# design.net
KiCad netlist of a schematic drawn in Altium Designer
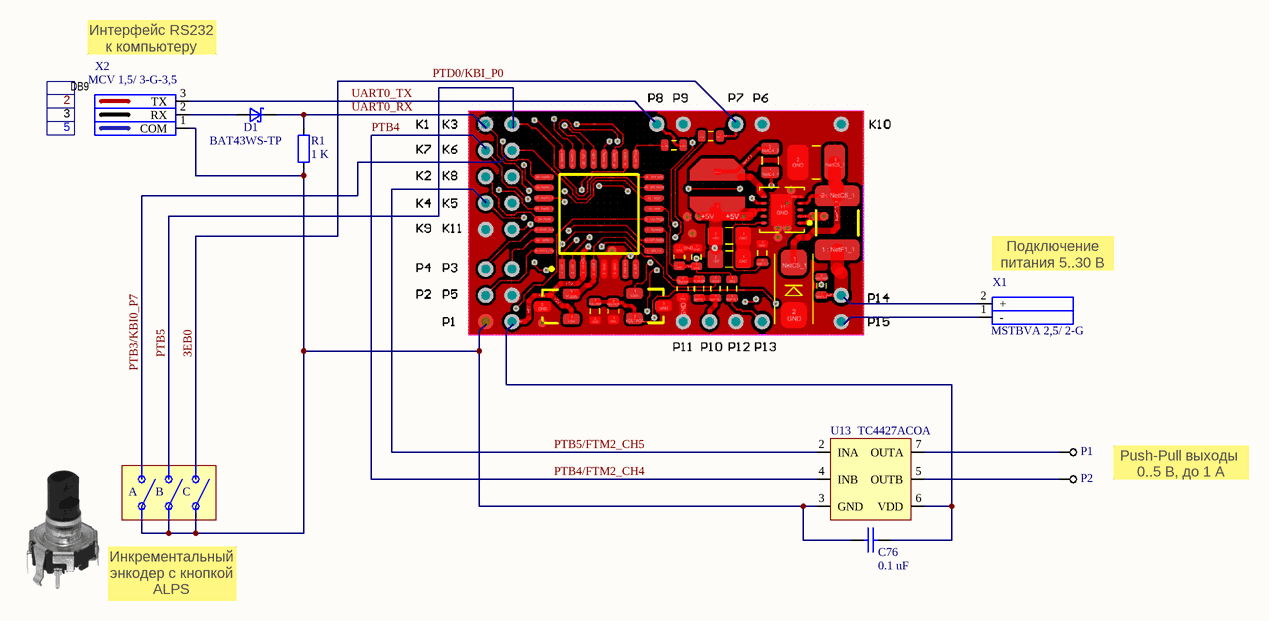
[diagram p0: Макет генератора сигналов.SchDoc]

(export (version "E")
  (design (tool "Eeschema 10.0.6"))
  (components
    (comp (ref "C76")
      (value "0.1 uF")
      (footprint "1608[0603]")
      (description "0.1 uF, 25V, 10% , X7R,  0603 SMD MLC Capacitor")
      (fields (field (name "TOLERANCE") "10%") (field (name "MANUFACTURER") "SAMSUNG"))
      (libsource (lib "ea_Capacitors") (part "CVNF100K0603-25"))
    )
    (comp (ref "D1")
      (value "BAT43WS-TP")
      (footprint "SOD323")
      (description "Schottky 30V 200 mA SOD323")
      (fields
        (field (name "MANUFACTURER") "Micro Commercial Co.")
        (field (name "PARTNUM") "BAT43WSTPMSCT-ND")
      )
      (libsource (lib "ea_Diodes") (part "BAT43WS-TP"))
    )
    (comp (ref "P1")
      (value "Pin 0.7 mm")
      (footprint "Mount hole 0.7 mm")
      (libsource (lib "ea_Connectors") (part "Pin 0.7 mm"))
    )
    (comp (ref "P2")
      (value "Pin 0.7 mm")
      (footprint "Mount hole 0.7 mm")
      (libsource (lib "ea_Connectors") (part "Pin 0.7 mm"))
    )
    (comp (ref "R1")
      (value "1 K")
      (footprint "0603")
      (description "1 K, 1%, 0603, SMD Resistor, Taped")
      (fields (field (name "MANUFACTURER") "Vishay") (field (name "TOLERANCE") "1%"))
      (libsource (lib "ea_Resistors") (part "RL0603K001-1"))
    )
    (comp (ref "U13")
      (value "TC4427ACOA")
      (footprint "SO-8")
      (description "MOSFET drv 1.5A dual, 4.5-18 V,   8SOIC, 0-70 C")
      (fields (field (name "MANUFACTURER") "Microchip Technology") (field (name "PARTNUM") "TC4427ACOA-ND"))
      (libsource (lib "ea_IC_registers_buffers") (part "TC4427ACOA"))
    )
    (comp (ref "X1")
      (value "MSTBVA 2,5/ 2-G")
      (footprint "CIM020P1")
      (description "TERM BLOCK HEADER 2POS 5.0MM")
      (fields (field (name "MANUFACTURER") "Phoenix Contact") (field (name "PARTNUM") "1755516"))
      (libsource (lib "ea_Connectors") (part "796636-2"))
    )
    (comp (ref "X2")
      (value "MCV 1,5/ 3-G-3,5")
      (footprint "mcv1.5-3-g_3.5")
      (description "Header, 8 A, 160 V, 3.5 mm pitch, 3 pos")
      (fields (field (name "MANUFACTURER") "Phoenix Contact") (field (name "PARTNUM") "1843619"))
      (libsource (lib "ea_Connectors") (part "MCV1.5/3-G-3.5"))
    )
  )
  (nets
    (net (code "2") (name "/PTB4") (class "Default")
      (node (ref "U13") (pin "4") (pinfunction "INB_4") (pintype "passive"))
    )
    (net (code "4") (name "/PTB5{slash}FTM2_CH5") (class "Default")
      (node (ref "U13") (pin "2") (pinfunction "INA_2") (pintype "passive"))
    )
    (net (code "6") (name "/UART0_RX") (class "Default")
      (node (ref "D1") (pin "2") (pinfunction "C_2") (pintype "passive"))
      (node (ref "R1") (pin "2") (pinfunction "2_2") (pintype "passive"))
    )
    (net (code "7") (name "/UART0_TX") (class "Default")
      (node (ref "X2") (pin "3") (pinfunction "TX_3") (pintype "passive"))
    )
    (net (code "8") (name "Net-(D1-A)") (class "Default")
      (node (ref "D1") (pin "1") (pinfunction "A_1") (pintype "passive"))
      (node (ref "X2") (pin "2") (pinfunction "RX_2") (pintype "passive"))
    )
    (net (code "9") (name "Net-(U13-GND)") (class "Default")
      (node (ref "C76") (pin "1") (pinfunction "1_1") (pintype "passive"))
      (node (ref "R1") (pin "1") (pinfunction "1_1") (pintype "passive"))
      (node (ref "U13") (pin "3") (pinfunction "GND_3") (pintype "passive"))
      (node (ref "X2") (pin "1") (pinfunction "COM_1") (pintype "passive"))
    )
    (net (code "10") (name "Net-(U13-OUTA)") (class "Default")
      (node (ref "P1") (pin "1") (pinfunction "1_1") (pintype "passive"))
      (node (ref "U13") (pin "7") (pinfunction "OUTA_7") (pintype "passive"))
    )
    (net (code "11") (name "Net-(U13-OUTB)") (class "Default")
      (node (ref "P2") (pin "1") (pinfunction "1_1") (pintype "passive"))
      (node (ref "U13") (pin "5") (pinfunction "OUTB_5") (pintype "passive"))
    )
    (net (code "12") (name "Net-(U13-VDD)") (class "Default")
      (node (ref "C76") (pin "2") (pinfunction "2_2") (pintype "passive"))
      (node (ref "U13") (pin "6") (pinfunction "VDD_6") (pintype "passive"))
    )
    (net (code "13") (name "unconnected-(X1-+-Pad2)") (class "Default")
      (node (ref "X1") (pin "2") (pinfunction "+_2") (pintype "passive"))
    )
    (net (code "14") (name "unconnected-(X1---Pad1)") (class "Default")
      (node (ref "X1") (pin "1") (pinfunction "-_1") (pintype "passive"))
    )
  )
)
